# TTAmp_3T0K_amp_tensometer_2.net
KiCad netlist of a schematic drawn in Altium Designer
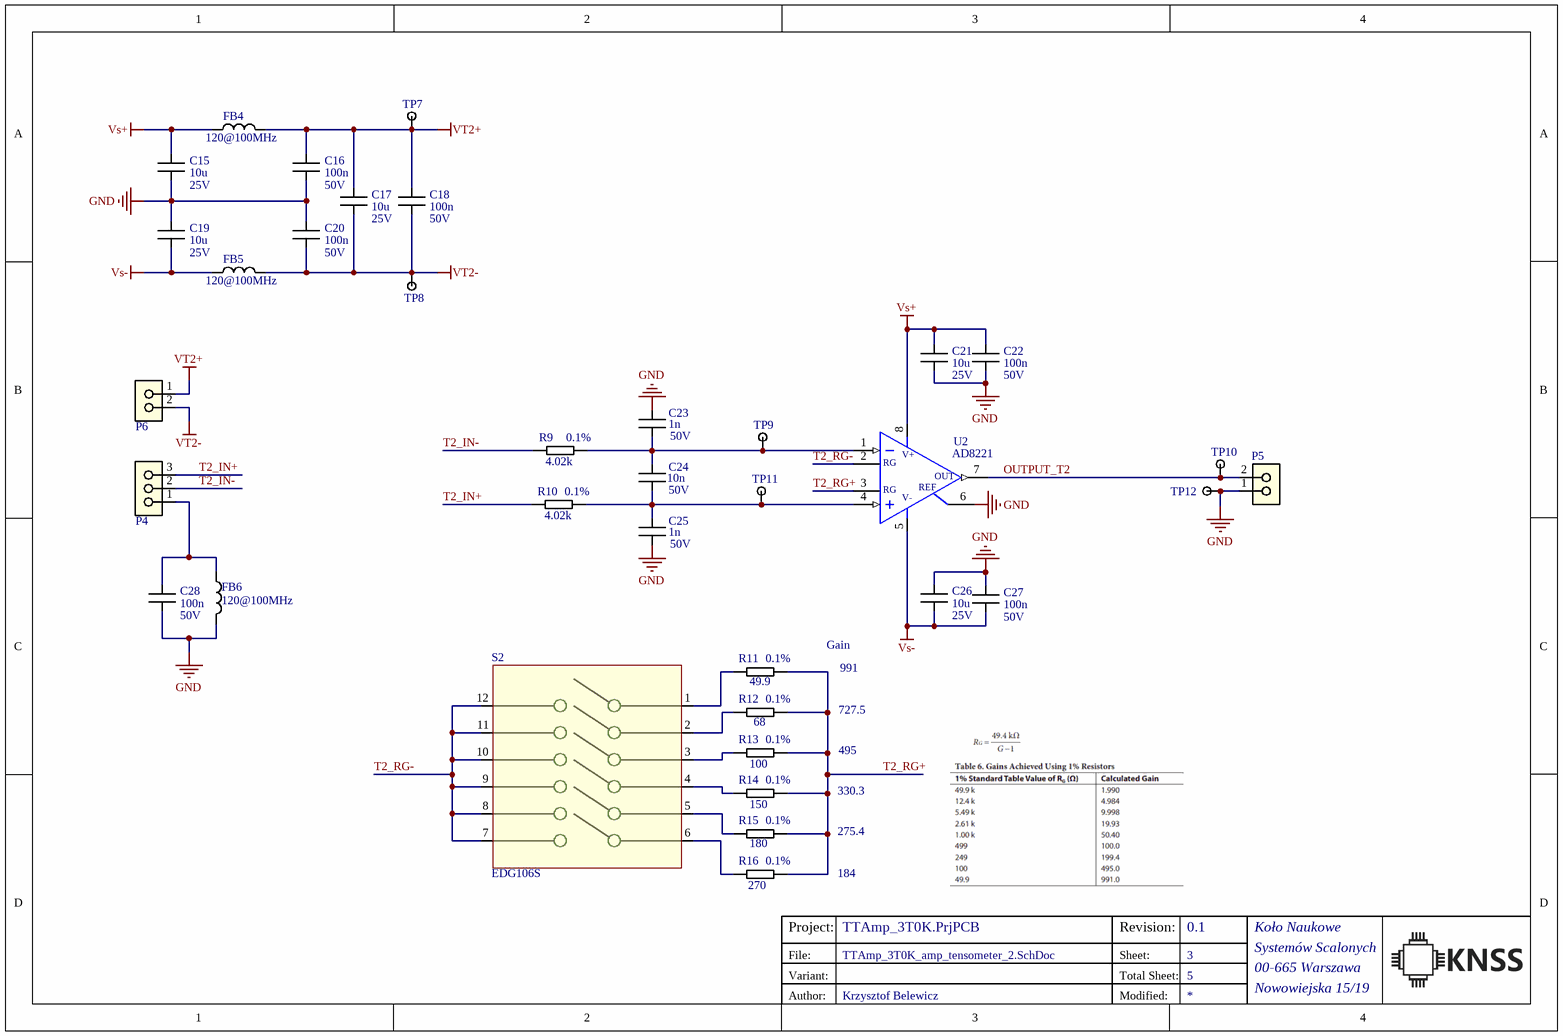
[diagram p0: TTAmp_3T0K_amp_tensometer_2.SchDoc]

(export (version "E")
  (design (tool "Eeschema 10.0.6"))
  (components
    (comp (ref "C15")
      (value "10u")
      (footprint "CAPC2012N")
      (description "Capacitor")
      (fields (field (name "TOLERANCE") "10%") (field (name "MAXVOLTAGE") "25V"))
      (libsource (lib "RLC") (part "Capacitor"))
    )
    (comp (ref "C16")
      (value "100n")
      (footprint "CAPC1608N")
      (description "Capacitor")
      (fields (field (name "TOLERANCE") "10%") (field (name "MAXVOLTAGE") "50V"))
      (libsource (lib "RLC") (part "Capacitor"))
    )
    (comp (ref "C17")
      (value "10u")
      (footprint "CAPC2012N")
      (description "Capacitor")
      (fields (field (name "TOLERANCE") "10%") (field (name "MAXVOLTAGE") "25V"))
      (libsource (lib "RLC") (part "Capacitor"))
    )
    (comp (ref "C18")
      (value "100n")
      (footprint "CAPC1608N")
      (description "Capacitor")
      (fields (field (name "TOLERANCE") "10%") (field (name "MAXVOLTAGE") "50V"))
      (libsource (lib "RLC") (part "Capacitor"))
    )
    (comp (ref "C19")
      (value "10u")
      (footprint "CAPC2012N")
      (description "Capacitor")
      (fields (field (name "TOLERANCE") "10%") (field (name "MAXVOLTAGE") "25V"))
      (libsource (lib "RLC") (part "Capacitor"))
    )
    (comp (ref "C20")
      (value "100n")
      (footprint "CAPC1608N")
      (description "Capacitor")
      (fields (field (name "TOLERANCE") "10%") (field (name "MAXVOLTAGE") "50V"))
      (libsource (lib "RLC") (part "Capacitor"))
    )
    (comp (ref "C21")
      (value "10u")
      (footprint "CAPC2012N")
      (description "Capacitor")
      (fields (field (name "TOLERANCE") "10%") (field (name "MAXVOLTAGE") "25V"))
      (libsource (lib "RLC") (part "Capacitor"))
    )
    (comp (ref "C22")
      (value "100n")
      (footprint "CAPC1608N")
      (description "Capacitor")
      (fields (field (name "TOLERANCE") "10%") (field (name "MAXVOLTAGE") "50V"))
      (libsource (lib "RLC") (part "Capacitor"))
    )
    (comp (ref "C23")
      (value "1n")
      (footprint "CAPC1608N")
      (description "Capacitor")
      (fields (field (name "TOLERANCE") "10%") (field (name "MAXVOLTAGE") "50V"))
      (libsource (lib "RLC") (part "Capacitor"))
    )
    (comp (ref "C24")
      (value "10n")
      (footprint "CAPC1608N")
      (description "Capacitor")
      (fields (field (name "TOLERANCE") "20%") (field (name "MAXVOLTAGE") "50V"))
      (libsource (lib "RLC") (part "Capacitor"))
    )
    (comp (ref "C25")
      (value "1n")
      (footprint "CAPC1608N")
      (description "Capacitor")
      (fields (field (name "TOLERANCE") "10%") (field (name "MAXVOLTAGE") "50V"))
      (libsource (lib "RLC") (part "Capacitor"))
    )
    (comp (ref "C26")
      (value "10u")
      (footprint "CAPC2012N")
      (description "Capacitor")
      (fields (field (name "TOLERANCE") "10%") (field (name "MAXVOLTAGE") "25V"))
      (libsource (lib "RLC") (part "Capacitor"))
    )
    (comp (ref "C27")
      (value "100n")
      (footprint "CAPC1608N")
      (description "Capacitor")
      (fields (field (name "TOLERANCE") "10%") (field (name "MAXVOLTAGE") "50V"))
      (libsource (lib "RLC") (part "Capacitor"))
    )
    (comp (ref "C28")
      (value "100n")
      (footprint "CAPC1608N")
      (description "Capacitor")
      (fields (field (name "TOLERANCE") "10%") (field (name "MAXVOLTAGE") "50V"))
      (libsource (lib "RLC") (part "Capacitor"))
    )
    (comp (ref "FB4")
      (value "120@100MHz")
      (footprint "INDC1608N")
      (description "Ferrite Bead")
      (libsource (lib "") (part "Inductor_1"))
    )
    (comp (ref "FB5")
      (value "120@100MHz")
      (footprint "INDC1608N")
      (description "Ferrite Bead")
      (libsource (lib "") (part "Inductor_1"))
    )
    (comp (ref "FB6")
      (value "120@100MHz")
      (footprint "INDC1608N")
      (description "Ferrite Bead")
      (libsource (lib "RLC") (part "Inductor"))
    )
    (comp (ref "P4")
      (value "AK100/3DS-5,0-V/GRAU")
      (footprint "AK100/3DS-5,0-V/GRAU")
      (description "Listwa zaciskowa do druku; kątowe 90°; 5mm; tory:3; na PCB; 24A")
      (fields (field (name "MANUFACTURER") "PTR MESSTECHNIK"))
      (libsource (lib "Screw Terminals") (part "AK100/3DS-5,0-V/GRAU"))
    )
    (comp (ref "P5")
      (value "AK100/2DS-5,0-V/GRAU")
      (footprint "AK100/2DS-5,0-V/GRAU")
      (description "Listwa zaciskowa do druku; kątowe 90°; 5mm; tory:2; na PCB; 24A")
      (fields (field (name "MANUFACTURER") "PTR MESSTECHNIK"))
      (libsource (lib "") (part "AK100/2DS-5,0-V/GRAU_1"))
    )
    (comp (ref "P6")
      (value "AK100/2DS-5,0-V/GRAU")
      (footprint "AK100/2DS-5,0-V/GRAU")
      (description "Listwa zaciskowa do druku; kątowe 90°; 5mm; tory:2; na PCB; 24A")
      (fields (field (name "MANUFACTURER") "PTR MESSTECHNIK"))
      (libsource (lib "Screw Terminals") (part "AK100/2DS-5,0-V/GRAU"))
    )
    (comp (ref "R9")
      (value "4.02k")
      (footprint "RESC1608N")
      (description "Resistor")
      (fields (field (name "TOLERANCE") "0.1%") (field (name "POWER") "0.1W"))
      (libsource (lib "RLC") (part "Resistor"))
    )
    (comp (ref "R10")
      (value "4.02k")
      (footprint "RESC1608N")
      (description "Resistor")
      (fields (field (name "TOLERANCE") "0.1%") (field (name "POWER") "0.1W"))
      (libsource (lib "RLC") (part "Resistor"))
    )
    (comp (ref "R11")
      (value "49.9")
      (footprint "RESC1608N")
      (description "Resistor")
      (fields (field (name "TOLERANCE") "0.1%") (field (name "POWER") "0.1W"))
      (libsource (lib "RLC") (part "Resistor"))
    )
    (comp (ref "R12")
      (value "68")
      (footprint "RESC1608N")
      (description "Resistor")
      (fields
        (field (name "TOLERANCE") "0.1%")
        (field (name "POWER") "0.1W")
        (field (name "MANUFACTURER") "VIKING")
      )
      (libsource (lib "RLC") (part "Resistor"))
    )
    (comp (ref "R13")
      (value "100")
      (footprint "RESC1608N")
      (description "Resistor")
      (fields (field (name "TOLERANCE") "0.1%") (field (name "POWER") "0.1W"))
      (libsource (lib "RLC") (part "Resistor"))
    )
    (comp (ref "R14")
      (value "150")
      (footprint "RESC1608N")
      (description "Resistor")
      (fields (field (name "TOLERANCE") "0.1%") (field (name "POWER") "0.1W"))
      (libsource (lib "RLC") (part "Resistor"))
    )
    (comp (ref "R15")
      (value "180")
      (footprint "RESC1608N")
      (description "Resistor")
      (fields (field (name "TOLERANCE") "0.1%") (field (name "POWER") "0.1W"))
      (libsource (lib "RLC") (part "Resistor"))
    )
    (comp (ref "R16")
      (value "270")
      (footprint "RESC1608N")
      (description "Resistor")
      (fields (field (name "TOLERANCE") "0.1%") (field (name "POWER") "0.1W"))
      (libsource (lib "RLC") (part "Resistor"))
    )
    (comp (ref "S2")
      (value "EDG106S")
      (footprint "EDG106S")
      (description "Przełącznik: DIP-SWITCH; Ilość sekcji:6; ON-OFF; 0,1A/24VDC; 500V")
      (libsource (lib "ECE") (part "EDG106S"))
    )
    (comp (ref "TP7")
      (value "~")
      (footprint "TP-SMD-1.0MM")
      (description "Test Point for probe")
      (libsource (lib "TestPoints") (part "TP1"))
    )
    (comp (ref "TP8")
      (value "~")
      (footprint "TP-SMD-1.0MM")
      (description "Test Point for probe")
      (libsource (lib "TestPoints") (part "TP1"))
    )
    (comp (ref "TP9")
      (value "~")
      (footprint "TP-SMD-1.0MM")
      (description "Test Point for probe")
      (libsource (lib "TestPoints") (part "TP1"))
    )
    (comp (ref "TP10")
      (value "~")
      (footprint "TP-SMD-1.0MM")
      (description "Test Point for probe")
      (libsource (lib "TestPoints") (part "TP1"))
    )
    (comp (ref "TP11")
      (value "~")
      (footprint "TP-SMD-1.0MM")
      (description "Test Point for probe")
      (libsource (lib "TestPoints") (part "TP1"))
    )
    (comp (ref "TP12")
      (value "~")
      (footprint "TP-SMD-1.0MM")
      (description "Test Point for probe")
      (libsource (lib "TestPoints") (part "TP1"))
    )
    (comp (ref "U2")
      (value "AD8221")
      (footprint "R-8_N")
      (description "Precision Instrumentation Amplifier")
      (libsource (lib "AD Instrumentation Amplifier") (part "AD8221"))
    )
  )
  (nets
    (net (code "1") (name "/OUTPUT_T2") (class "Default")
      (node (ref "P5") (pin "2") (pinfunction "2_2") (pintype "passive"))
      (node (ref "TP10") (pin "1") (pinfunction "1_1") (pintype "passive"))
      (node (ref "U2") (pin "7") (pinfunction "OUT_7") (pintype "output"))
    )
    (net (code "2") (name "/T2_IN+") (class "Default")
      (node (ref "P4") (pin "3") (pinfunction "3_3") (pintype "passive"))
      (node (ref "R10") (pin "2") (pinfunction "2_2") (pintype "passive"))
    )
    (net (code "3") (name "/T2_IN-") (class "Default")
      (node (ref "P4") (pin "2") (pinfunction "2_2") (pintype "passive"))
      (node (ref "R9") (pin "2") (pinfunction "2_2") (pintype "passive"))
    )
    (net (code "4") (name "/T2_RG+") (class "Default")
      (node (ref "R11") (pin "1") (pinfunction "1_1") (pintype "passive"))
      (node (ref "R12") (pin "1") (pinfunction "1_1") (pintype "passive"))
      (node (ref "R13") (pin "1") (pinfunction "1_1") (pintype "passive"))
      (node (ref "R14") (pin "1") (pinfunction "1_1") (pintype "passive"))
      (node (ref "R15") (pin "1") (pinfunction "1_1") (pintype "passive"))
      (node (ref "R16") (pin "1") (pinfunction "1_1") (pintype "passive"))
      (node (ref "U2") (pin "3") (pinfunction "RG_3") (pintype "passive"))
    )
    (net (code "5") (name "/T2_RG-") (class "Default")
      (node (ref "S2") (pin "10") (pinfunction "10_10") (pintype "passive"))
      (node (ref "S2") (pin "11") (pinfunction "11_11") (pintype "passive"))
      (node (ref "S2") (pin "12") (pinfunction "12_12") (pintype "passive"))
      (node (ref "S2") (pin "7") (pinfunction "13_7") (pintype "passive"))
      (node (ref "S2") (pin "8") (pinfunction "12_8") (pintype "passive"))
      (node (ref "S2") (pin "9") (pinfunction "11_9") (pintype "passive"))
      (node (ref "U2") (pin "2") (pinfunction "RG_2") (pintype "passive"))
    )
    (net (code "6") (name "GND") (class "Default")
      (node (ref "C15") (pin "1") (pinfunction "1_1") (pintype "passive"))
      (node (ref "C16") (pin "1") (pinfunction "1_1") (pintype "passive"))
      (node (ref "C19") (pin "2") (pinfunction "2_2") (pintype "passive"))
      (node (ref "C20") (pin "2") (pinfunction "2_2") (pintype "passive"))
      (node (ref "C21") (pin "1") (pinfunction "1_1") (pintype "passive"))
      (node (ref "C22") (pin "1") (pinfunction "1_1") (pintype "passive"))
      (node (ref "C23") (pin "2") (pinfunction "2_2") (pintype "passive"))
      (node (ref "C25") (pin "1") (pinfunction "1_1") (pintype "passive"))
      (node (ref "C26") (pin "2") (pinfunction "2_2") (pintype "passive"))
      (node (ref "C27") (pin "2") (pinfunction "2_2") (pintype "passive"))
      (node (ref "C28") (pin "1") (pinfunction "1_1") (pintype "passive"))
      (node (ref "FB6") (pin "2") (pinfunction "2_2") (pintype "passive"))
      (node (ref "P5") (pin "1") (pinfunction "1_1") (pintype "passive"))
      (node (ref "TP12") (pin "1") (pinfunction "1_1") (pintype "passive"))
      (node (ref "U2") (pin "6") (pinfunction "REF_6") (pintype "passive"))
    )
    (net (code "7") (name "Net-(C28-Pad2)") (class "Default")
      (node (ref "C28") (pin "2") (pinfunction "2_2") (pintype "passive"))
      (node (ref "FB6") (pin "1") (pinfunction "1_1") (pintype "passive"))
      (node (ref "P4") (pin "1") (pinfunction "1_1") (pintype "passive"))
    )
    (net (code "8") (name "Net-(R11-Pad2)") (class "Default")
      (node (ref "R11") (pin "2") (pinfunction "2_2") (pintype "passive"))
      (node (ref "S2") (pin "1") (pinfunction "1_1") (pintype "passive"))
    )
    (net (code "9") (name "Net-(R12-Pad2)") (class "Default")
      (node (ref "R12") (pin "2") (pinfunction "2_2") (pintype "passive"))
      (node (ref "S2") (pin "2") (pinfunction "2_2") (pintype "passive"))
    )
    (net (code "10") (name "Net-(R13-Pad2)") (class "Default")
      (node (ref "R13") (pin "2") (pinfunction "2_2") (pintype "passive"))
      (node (ref "S2") (pin "3") (pinfunction "3_3") (pintype "passive"))
    )
    (net (code "11") (name "Net-(R14-Pad2)") (class "Default")
      (node (ref "R14") (pin "2") (pinfunction "2_2") (pintype "passive"))
      (node (ref "S2") (pin "4") (pinfunction "4_4") (pintype "passive"))
    )
    (net (code "12") (name "Net-(R15-Pad2)") (class "Default")
      (node (ref "R15") (pin "2") (pinfunction "2_2") (pintype "passive"))
      (node (ref "S2") (pin "5") (pinfunction "5_5") (pintype "passive"))
    )
    (net (code "13") (name "Net-(R16-Pad2)") (class "Default")
      (node (ref "R16") (pin "2") (pinfunction "2_2") (pintype "passive"))
      (node (ref "S2") (pin "6") (pinfunction "6_6") (pintype "passive"))
    )
    (net (code "14") (name "Net-(U2-+IN)") (class "Default")
      (node (ref "C24") (pin "1") (pinfunction "1_1") (pintype "passive"))
      (node (ref "C25") (pin "2") (pinfunction "2_2") (pintype "passive"))
      (node (ref "R10") (pin "1") (pinfunction "1_1") (pintype "passive"))
      (node (ref "TP11") (pin "1") (pinfunction "1_1") (pintype "passive"))
      (node (ref "U2") (pin "4") (pinfunction "+IN_4") (pintype "input"))
    )
    (net (code "15") (name "Net-(U2--IN)") (class "Default")
      (node (ref "C23") (pin "1") (pinfunction "1_1") (pintype "passive"))
      (node (ref "C24") (pin "2") (pinfunction "2_2") (pintype "passive"))
      (node (ref "R9") (pin "1") (pinfunction "1_1") (pintype "passive"))
      (node (ref "TP9") (pin "1") (pinfunction "1_1") (pintype "passive"))
      (node (ref "U2") (pin "1") (pinfunction "-IN_1") (pintype "input"))
    )
    (net (code "16") (name "VT2+") (class "Default")
      (node (ref "C16") (pin "2") (pinfunction "2_2") (pintype "passive"))
      (node (ref "C17") (pin "2") (pinfunction "2_2") (pintype "passive"))
      (node (ref "C18") (pin "2") (pinfunction "2_2") (pintype "passive"))
      (node (ref "FB4") (pin "1") (pinfunction "1_1") (pintype "passive"))
      (node (ref "P6") (pin "1") (pinfunction "1_1") (pintype "passive"))
      (node (ref "TP7") (pin "1") (pinfunction "1_1") (pintype "passive"))
    )
    (net (code "17") (name "VT2-") (class "Default")
      (node (ref "C17") (pin "1") (pinfunction "1_1") (pintype "passive"))
      (node (ref "C18") (pin "1") (pinfunction "1_1") (pintype "passive"))
      (node (ref "C20") (pin "1") (pinfunction "1_1") (pintype "passive"))
      (node (ref "FB5") (pin "1") (pinfunction "1_1") (pintype "passive"))
      (node (ref "P6") (pin "2") (pinfunction "2_2") (pintype "passive"))
      (node (ref "TP8") (pin "1") (pinfunction "1_1") (pintype "passive"))
    )
    (net (code "18") (name "Vs+") (class "Default")
      (node (ref "C15") (pin "2") (pinfunction "2_2") (pintype "passive"))
      (node (ref "C21") (pin "2") (pinfunction "2_2") (pintype "passive"))
      (node (ref "C22") (pin "2") (pinfunction "2_2") (pintype "passive"))
      (node (ref "FB4") (pin "2") (pinfunction "2_2") (pintype "passive"))
      (node (ref "U2") (pin "8") (pinfunction "V+_8") (pintype "power_in"))
    )
    (net (code "19") (name "Vs-") (class "Default")
      (node (ref "C19") (pin "1") (pinfunction "1_1") (pintype "passive"))
      (node (ref "C26") (pin "1") (pinfunction "1_1") (pintype "passive"))
      (node (ref "C27") (pin "1") (pinfunction "1_1") (pintype "passive"))
      (node (ref "FB5") (pin "2") (pinfunction "2_2") (pintype "passive"))
      (node (ref "U2") (pin "5") (pinfunction "V-_5") (pintype "power_in"))
    )
  )
)
